# Sheet1.net
KiCad netlist of a schematic drawn in Altium Designer
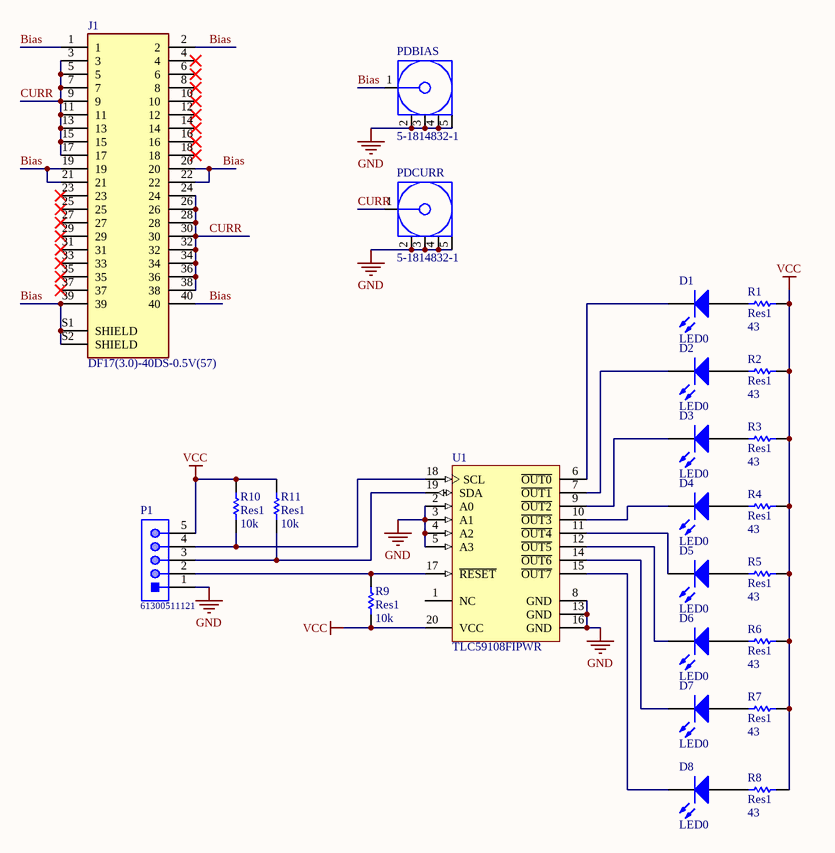
[diagram p0: Sheet1.SchDoc]

(export (version "E")
  (design (tool "Eeschema 10.0.6"))
  (components
    (comp (ref "D1")
      (value "LED0")
      (footprint "TO-18")
      (description "Typical INFRARED GaAs LED")
      (fields (field (name "PUBLISHER") "Altium Limited"))
      (libsource (lib "Miscellaneous Devices") (part "LED0"))
    )
    (comp (ref "D2")
      (value "LED0")
      (footprint "TO-18")
      (description "Typical INFRARED GaAs LED")
      (fields (field (name "PUBLISHER") "Altium Limited"))
      (libsource (lib "Miscellaneous Devices") (part "LED0"))
    )
    (comp (ref "D3")
      (value "LED0")
      (footprint "TO-18")
      (description "Typical INFRARED GaAs LED")
      (fields (field (name "PUBLISHER") "Altium Limited"))
      (libsource (lib "Miscellaneous Devices") (part "LED0"))
    )
    (comp (ref "D4")
      (value "LED0")
      (footprint "TO-18")
      (description "Typical INFRARED GaAs LED")
      (fields (field (name "PUBLISHER") "Altium Limited"))
      (libsource (lib "Miscellaneous Devices") (part "LED0"))
    )
    (comp (ref "D5")
      (value "LED0")
      (footprint "TO-18")
      (description "Typical INFRARED GaAs LED")
      (fields (field (name "PUBLISHER") "Altium Limited"))
      (libsource (lib "Miscellaneous Devices") (part "LED0"))
    )
    (comp (ref "D6")
      (value "LED0")
      (footprint "TO-18")
      (description "Typical INFRARED GaAs LED")
      (fields (field (name "PUBLISHER") "Altium Limited"))
      (libsource (lib "Miscellaneous Devices") (part "LED0"))
    )
    (comp (ref "D7")
      (value "LED0")
      (footprint "TO-18")
      (description "Typical INFRARED GaAs LED")
      (fields (field (name "PUBLISHER") "Altium Limited"))
      (libsource (lib "Miscellaneous Devices") (part "LED0"))
    )
    (comp (ref "D8")
      (value "LED0")
      (footprint "TO-18")
      (description "Typical INFRARED GaAs LED")
      (fields (field (name "PUBLISHER") "Altium Limited"))
      (libsource (lib "Miscellaneous Devices") (part "LED0"))
    )
    (comp (ref "J1")
      (value "DF17(3.0)-40DS-0.5V(57)")
      (footprint "HRS_DF17(3.0)-40DS-0.5V(57)")
      (description "Conn Board to Board RCP 40 POS 0.5mm Solder ST SMD Embossed T/R")
      (libsource (lib "DF17_3.0_-40DS-0.5V_57_") (part "DF17(3.0)-40DS-0.5V(57)"))
    )
    (comp (ref "P1")
      (value "61300511121")
      (footprint "61300511121")
      (description "THT Vertical Pin Header WR-PHD, Pitch 2.54 mm, Single Row, 5 pins")
      (fields (field (name "MANUFACTURER") "Wurth Elektronik") (field (name "PUBLISHER") "WurthElektronik"))
      (libsource (lib "Altium Content Vault") (part "WE-CN-1P-M-R5"))
    )
    (comp (ref "PDBIAS")
      (value "5-1814832-1")
      (footprint "TECO-5-1814832-1_V")
      (fields (field (name "MANUFACTURER") "TE Connectivity"))
      (libsource (lib "Altium Content Vault") (part "CN-S-4F-RF5"))
    )
    (comp (ref "PDCURR")
      (value "5-1814832-1")
      (footprint "TECO-5-1814832-1_V")
      (fields (field (name "MANUFACTURER") "TE Connectivity"))
      (libsource (lib "Altium Content Vault") (part "CN-S-4F-RF5"))
    )
    (comp (ref "R1")
      (value "Res1")
      (footprint "6-0805_L")
      (description "Resistor")
      (fields (field (name "ALTIUM_VALUE") "43") (field (name "PUBLISHER") "Altium Limited"))
      (libsource (lib "Miscellaneous Devices") (part "Res1"))
    )
    (comp (ref "R2")
      (value "Res1")
      (footprint "6-0805_L")
      (description "Resistor")
      (fields (field (name "ALTIUM_VALUE") "43") (field (name "PUBLISHER") "Altium Limited"))
      (libsource (lib "Miscellaneous Devices") (part "Res1"))
    )
    (comp (ref "R3")
      (value "Res1")
      (footprint "6-0805_L")
      (description "Resistor")
      (fields (field (name "ALTIUM_VALUE") "43") (field (name "PUBLISHER") "Altium Limited"))
      (libsource (lib "Miscellaneous Devices") (part "Res1"))
    )
    (comp (ref "R4")
      (value "Res1")
      (footprint "6-0805_L")
      (description "Resistor")
      (fields (field (name "ALTIUM_VALUE") "43") (field (name "PUBLISHER") "Altium Limited"))
      (libsource (lib "Miscellaneous Devices") (part "Res1"))
    )
    (comp (ref "R5")
      (value "Res1")
      (footprint "6-0805_L")
      (description "Resistor")
      (fields (field (name "ALTIUM_VALUE") "43") (field (name "PUBLISHER") "Altium Limited"))
      (libsource (lib "Miscellaneous Devices") (part "Res1"))
    )
    (comp (ref "R6")
      (value "Res1")
      (footprint "6-0805_L")
      (description "Resistor")
      (fields (field (name "ALTIUM_VALUE") "43") (field (name "PUBLISHER") "Altium Limited"))
      (libsource (lib "Miscellaneous Devices") (part "Res1"))
    )
    (comp (ref "R7")
      (value "Res1")
      (footprint "6-0805_L")
      (description "Resistor")
      (fields (field (name "ALTIUM_VALUE") "43") (field (name "PUBLISHER") "Altium Limited"))
      (libsource (lib "Miscellaneous Devices") (part "Res1"))
    )
    (comp (ref "R8")
      (value "Res1")
      (footprint "6-0805_L")
      (description "Resistor")
      (fields (field (name "ALTIUM_VALUE") "43") (field (name "PUBLISHER") "Altium Limited"))
      (libsource (lib "Miscellaneous Devices") (part "Res1"))
    )
    (comp (ref "R9")
      (value "Res1")
      (footprint "6-0805_L")
      (description "Resistor")
      (fields (field (name "ALTIUM_VALUE") "10k") (field (name "PUBLISHER") "Altium Limited"))
      (libsource (lib "Miscellaneous Devices") (part "Res1"))
    )
    (comp (ref "R10")
      (value "Res1")
      (footprint "6-0805_L")
      (description "Resistor")
      (fields (field (name "ALTIUM_VALUE") "10k") (field (name "PUBLISHER") "Altium Limited"))
      (libsource (lib "Miscellaneous Devices") (part "Res1"))
    )
    (comp (ref "R11")
      (value "Res1")
      (footprint "6-0805_L")
      (description "Resistor")
      (fields (field (name "ALTIUM_VALUE") "10k") (field (name "PUBLISHER") "Altium Limited"))
      (libsource (lib "Miscellaneous Devices") (part "Res1"))
    )
    (comp (ref "U1")
      (value "TLC59108FIPWR")
      (footprint "PW0020A_L")
      (fields (field (name "MANUFACTURER") "Texas Instruments"))
      (libsource (lib "Altium Content Vault") (part "TI-TLC59108FPW20"))
    )
  )
  (nets
    (net (code "1") (name "/Bias") (class "Default")
      (node (ref "J1") (pin "1") (pinfunction "1_1") (pintype "passive"))
      (node (ref "J1") (pin "19") (pinfunction "19_19") (pintype "passive"))
      (node (ref "J1") (pin "2") (pinfunction "2_2") (pintype "passive"))
      (node (ref "J1") (pin "20") (pinfunction "20_20") (pintype "passive"))
      (node (ref "J1") (pin "21") (pinfunction "21_21") (pintype "passive"))
      (node (ref "J1") (pin "22") (pinfunction "22_22") (pintype "passive"))
      (node (ref "J1") (pin "39") (pinfunction "39_39") (pintype "passive"))
      (node (ref "J1") (pin "40") (pinfunction "40_40") (pintype "passive"))
      (node (ref "J1") (pin "S1") (pinfunction "SHIELD_S1") (pintype "passive"))
      (node (ref "J1") (pin "S2") (pinfunction "SHIELD_S2") (pintype "passive"))
      (node (ref "PDBIAS") (pin "1") (pinfunction "1_1") (pintype "passive"))
    )
    (net (code "2") (name "/CURR") (class "Default")
      (node (ref "J1") (pin "11") (pinfunction "11_11") (pintype "passive"))
      (node (ref "J1") (pin "13") (pinfunction "13_13") (pintype "passive"))
      (node (ref "J1") (pin "15") (pinfunction "15_15") (pintype "passive"))
      (node (ref "J1") (pin "17") (pinfunction "17_17") (pintype "passive"))
      (node (ref "J1") (pin "24") (pinfunction "24_24") (pintype "passive"))
      (node (ref "J1") (pin "26") (pinfunction "26_26") (pintype "passive"))
      (node (ref "J1") (pin "28") (pinfunction "28_28") (pintype "passive"))
      (node (ref "J1") (pin "3") (pinfunction "3_3") (pintype "passive"))
      (node (ref "J1") (pin "30") (pinfunction "30_30") (pintype "passive"))
      (node (ref "J1") (pin "32") (pinfunction "32_32") (pintype "passive"))
      (node (ref "J1") (pin "34") (pinfunction "34_34") (pintype "passive"))
      (node (ref "J1") (pin "36") (pinfunction "36_36") (pintype "passive"))
      (node (ref "J1") (pin "38") (pinfunction "38_38") (pintype "passive"))
      (node (ref "J1") (pin "5") (pinfunction "5_5") (pintype "passive"))
      (node (ref "J1") (pin "7") (pinfunction "7_7") (pintype "passive"))
      (node (ref "J1") (pin "9") (pinfunction "9_9") (pintype "passive"))
      (node (ref "PDCURR") (pin "1") (pinfunction "1_1") (pintype "passive"))
    )
    (net (code "3") (name "GND") (class "Default")
      (node (ref "P1") (pin "1") (pinfunction "1_1") (pintype "passive"))
      (node (ref "PDBIAS") (pin "2") (pinfunction "2_2") (pintype "passive"))
      (node (ref "PDBIAS") (pin "3") (pinfunction "3_3") (pintype "passive"))
      (node (ref "PDBIAS") (pin "4") (pinfunction "4_4") (pintype "passive"))
      (node (ref "PDBIAS") (pin "5") (pinfunction "5_5") (pintype "passive"))
      (node (ref "PDCURR") (pin "2") (pinfunction "2_2") (pintype "passive"))
      (node (ref "PDCURR") (pin "3") (pinfunction "3_3") (pintype "passive"))
      (node (ref "PDCURR") (pin "4") (pinfunction "4_4") (pintype "passive"))
      (node (ref "PDCURR") (pin "5") (pinfunction "5_5") (pintype "passive"))
      (node (ref "U1") (pin "13") (pinfunction "GND_13") (pintype "power_in"))
      (node (ref "U1") (pin "16") (pinfunction "GND_16") (pintype "power_in"))
      (node (ref "U1") (pin "2") (pinfunction "A0_2") (pintype "input"))
      (node (ref "U1") (pin "3") (pinfunction "A1_3") (pintype "input"))
      (node (ref "U1") (pin "4") (pinfunction "A2_4") (pintype "input"))
      (node (ref "U1") (pin "5") (pinfunction "A3_5") (pintype "input"))
      (node (ref "U1") (pin "8") (pinfunction "GND_8") (pintype "power_in"))
    )
    (net (code "4") (name "Net-(D1-A)") (class "Default")
      (node (ref "D1") (pin "1") (pinfunction "A_1") (pintype "passive"))
      (node (ref "R1") (pin "1") (pinfunction "1_1") (pintype "passive"))
    )
    (net (code "5") (name "Net-(D1-K)") (class "Default")
      (node (ref "D1") (pin "2") (pinfunction "K_2") (pintype "passive"))
      (node (ref "U1") (pin "6") (pinfunction "~{OUT0}_6") (pintype "open_collector"))
    )
    (net (code "6") (name "Net-(D2-A)") (class "Default")
      (node (ref "D2") (pin "1") (pinfunction "A_1") (pintype "passive"))
      (node (ref "R2") (pin "1") (pinfunction "1_1") (pintype "passive"))
    )
    (net (code "7") (name "Net-(D2-K)") (class "Default")
      (node (ref "D2") (pin "2") (pinfunction "K_2") (pintype "passive"))
      (node (ref "U1") (pin "7") (pinfunction "~{OUT1}_7") (pintype "open_collector"))
    )
    (net (code "8") (name "Net-(D3-A)") (class "Default")
      (node (ref "D3") (pin "1") (pinfunction "A_1") (pintype "passive"))
      (node (ref "R3") (pin "1") (pinfunction "1_1") (pintype "passive"))
    )
    (net (code "9") (name "Net-(D3-K)") (class "Default")
      (node (ref "D3") (pin "2") (pinfunction "K_2") (pintype "passive"))
      (node (ref "U1") (pin "9") (pinfunction "~{OUT2}_9") (pintype "open_collector"))
    )
    (net (code "10") (name "Net-(D4-A)") (class "Default")
      (node (ref "D4") (pin "1") (pinfunction "A_1") (pintype "passive"))
      (node (ref "R4") (pin "1") (pinfunction "1_1") (pintype "passive"))
    )
    (net (code "11") (name "Net-(D4-K)") (class "Default")
      (node (ref "D4") (pin "2") (pinfunction "K_2") (pintype "passive"))
      (node (ref "U1") (pin "10") (pinfunction "~{OUT3}_10") (pintype "open_collector"))
    )
    (net (code "12") (name "Net-(D5-A)") (class "Default")
      (node (ref "D5") (pin "1") (pinfunction "A_1") (pintype "passive"))
      (node (ref "R5") (pin "1") (pinfunction "1_1") (pintype "passive"))
    )
    (net (code "13") (name "Net-(D5-K)") (class "Default")
      (node (ref "D5") (pin "2") (pinfunction "K_2") (pintype "passive"))
      (node (ref "U1") (pin "11") (pinfunction "~{OUT4}_11") (pintype "open_collector"))
    )
    (net (code "14") (name "Net-(D6-A)") (class "Default")
      (node (ref "D6") (pin "1") (pinfunction "A_1") (pintype "passive"))
      (node (ref "R6") (pin "1") (pinfunction "1_1") (pintype "passive"))
    )
    (net (code "15") (name "Net-(D6-K)") (class "Default")
      (node (ref "D6") (pin "2") (pinfunction "K_2") (pintype "passive"))
      (node (ref "U1") (pin "12") (pinfunction "~{OUT5}_12") (pintype "open_collector"))
    )
    (net (code "16") (name "Net-(D7-A)") (class "Default")
      (node (ref "D7") (pin "1") (pinfunction "A_1") (pintype "passive"))
      (node (ref "R7") (pin "1") (pinfunction "1_1") (pintype "passive"))
    )
    (net (code "17") (name "Net-(D7-K)") (class "Default")
      (node (ref "D7") (pin "2") (pinfunction "K_2") (pintype "passive"))
      (node (ref "U1") (pin "14") (pinfunction "~{OUT6}_14") (pintype "open_collector"))
    )
    (net (code "18") (name "Net-(D8-A)") (class "Default")
      (node (ref "D8") (pin "1") (pinfunction "A_1") (pintype "passive"))
      (node (ref "R8") (pin "1") (pinfunction "1_1") (pintype "passive"))
    )
    (net (code "19") (name "Net-(D8-K)") (class "Default")
      (node (ref "D8") (pin "2") (pinfunction "K_2") (pintype "passive"))
      (node (ref "U1") (pin "15") (pinfunction "~{OUT7}_15") (pintype "open_collector"))
    )
    (net (code "20") (name "Net-(U1-SCL)") (class "Default")
      (node (ref "P1") (pin "4") (pinfunction "4_4") (pintype "passive"))
      (node (ref "R10") (pin "2") (pinfunction "2_2") (pintype "passive"))
      (node (ref "U1") (pin "18") (pinfunction "SCL_18") (pintype "input"))
    )
    (net (code "21") (name "Net-(U1-SDA)") (class "Default")
      (node (ref "P1") (pin "3") (pinfunction "3_3") (pintype "passive"))
      (node (ref "R11") (pin "2") (pinfunction "2_2") (pintype "passive"))
      (node (ref "U1") (pin "19") (pinfunction "SDA_19") (pintype "bidirectional"))
    )
    (net (code "22") (name "Net-(U1-~{RESET})") (class "Default")
      (node (ref "P1") (pin "2") (pinfunction "2_2") (pintype "passive"))
      (node (ref "R9") (pin "1") (pinfunction "1_1") (pintype "passive"))
      (node (ref "U1") (pin "17") (pinfunction "~{RESET}_17") (pintype "input"))
    )
    (net (code "23") (name "VCC") (class "Default")
      (node (ref "P1") (pin "5") (pinfunction "5_5") (pintype "passive"))
      (node (ref "R1") (pin "2") (pinfunction "2_2") (pintype "passive"))
      (node (ref "R10") (pin "1") (pinfunction "1_1") (pintype "passive"))
      (node (ref "R11") (pin "1") (pinfunction "1_1") (pintype "passive"))
      (node (ref "R2") (pin "2") (pinfunction "2_2") (pintype "passive"))
      (node (ref "R3") (pin "2") (pinfunction "2_2") (pintype "passive"))
      (node (ref "R4") (pin "2") (pinfunction "2_2") (pintype "passive"))
      (node (ref "R5") (pin "2") (pinfunction "2_2") (pintype "passive"))
      (node (ref "R6") (pin "2") (pinfunction "2_2") (pintype "passive"))
      (node (ref "R7") (pin "2") (pinfunction "2_2") (pintype "passive"))
      (node (ref "R8") (pin "2") (pinfunction "2_2") (pintype "passive"))
      (node (ref "R9") (pin "2") (pinfunction "2_2") (pintype "passive"))
      (node (ref "U1") (pin "20") (pinfunction "VCC_20") (pintype "power_in"))
    )
    (net (code "24") (name "unconnected-(J1-Pad4)") (class "Default")
      (node (ref "J1") (pin "4") (pinfunction "4_4") (pintype "passive+no_connect"))
    )
    (net (code "25") (name "unconnected-(J1-Pad6)") (class "Default")
      (node (ref "J1") (pin "6") (pinfunction "6_6") (pintype "passive+no_connect"))
    )
    (net (code "26") (name "unconnected-(J1-Pad8)") (class "Default")
      (node (ref "J1") (pin "8") (pinfunction "8_8") (pintype "passive+no_connect"))
    )
    (net (code "27") (name "unconnected-(J1-Pad10)") (class "Default")
      (node (ref "J1") (pin "10") (pinfunction "10_10") (pintype "passive+no_connect"))
    )
    (net (code "28") (name "unconnected-(J1-Pad12)") (class "Default")
      (node (ref "J1") (pin "12") (pinfunction "12_12") (pintype "passive+no_connect"))
    )
    (net (code "29") (name "unconnected-(J1-Pad14)") (class "Default")
      (node (ref "J1") (pin "14") (pinfunction "14_14") (pintype "passive+no_connect"))
    )
    (net (code "30") (name "unconnected-(J1-Pad16)") (class "Default")
      (node (ref "J1") (pin "16") (pinfunction "16_16") (pintype "passive+no_connect"))
    )
    (net (code "31") (name "unconnected-(J1-Pad18)") (class "Default")
      (node (ref "J1") (pin "18") (pinfunction "18_18") (pintype "passive+no_connect"))
    )
    (net (code "32") (name "unconnected-(J1-Pad23)") (class "Default")
      (node (ref "J1") (pin "23") (pinfunction "23_23") (pintype "passive+no_connect"))
    )
    (net (code "33") (name "unconnected-(J1-Pad25)") (class "Default")
      (node (ref "J1") (pin "25") (pinfunction "25_25") (pintype "passive+no_connect"))
    )
    (net (code "34") (name "unconnected-(J1-Pad27)") (class "Default")
      (node (ref "J1") (pin "27") (pinfunction "27_27") (pintype "passive+no_connect"))
    )
    (net (code "35") (name "unconnected-(J1-Pad29)") (class "Default")
      (node (ref "J1") (pin "29") (pinfunction "29_29") (pintype "passive+no_connect"))
    )
    (net (code "36") (name "unconnected-(J1-Pad31)") (class "Default")
      (node (ref "J1") (pin "31") (pinfunction "31_31") (pintype "passive+no_connect"))
    )
    (net (code "37") (name "unconnected-(J1-Pad33)") (class "Default")
      (node (ref "J1") (pin "33") (pinfunction "33_33") (pintype "passive+no_connect"))
    )
    (net (code "38") (name "unconnected-(J1-Pad35)") (class "Default")
      (node (ref "J1") (pin "35") (pinfunction "35_35") (pintype "passive+no_connect"))
    )
    (net (code "39") (name "unconnected-(J1-Pad37)") (class "Default")
      (node (ref "J1") (pin "37") (pinfunction "37_37") (pintype "passive+no_connect"))
    )
    (net (code "40") (name "unconnected-(U1-NC-Pad1)") (class "Default")
      (node (ref "U1") (pin "1") (pinfunction "NC_1") (pintype "passive"))
    )
  )
)
